# main.net
KiCad netlist of a schematic drawn in Altium Designer
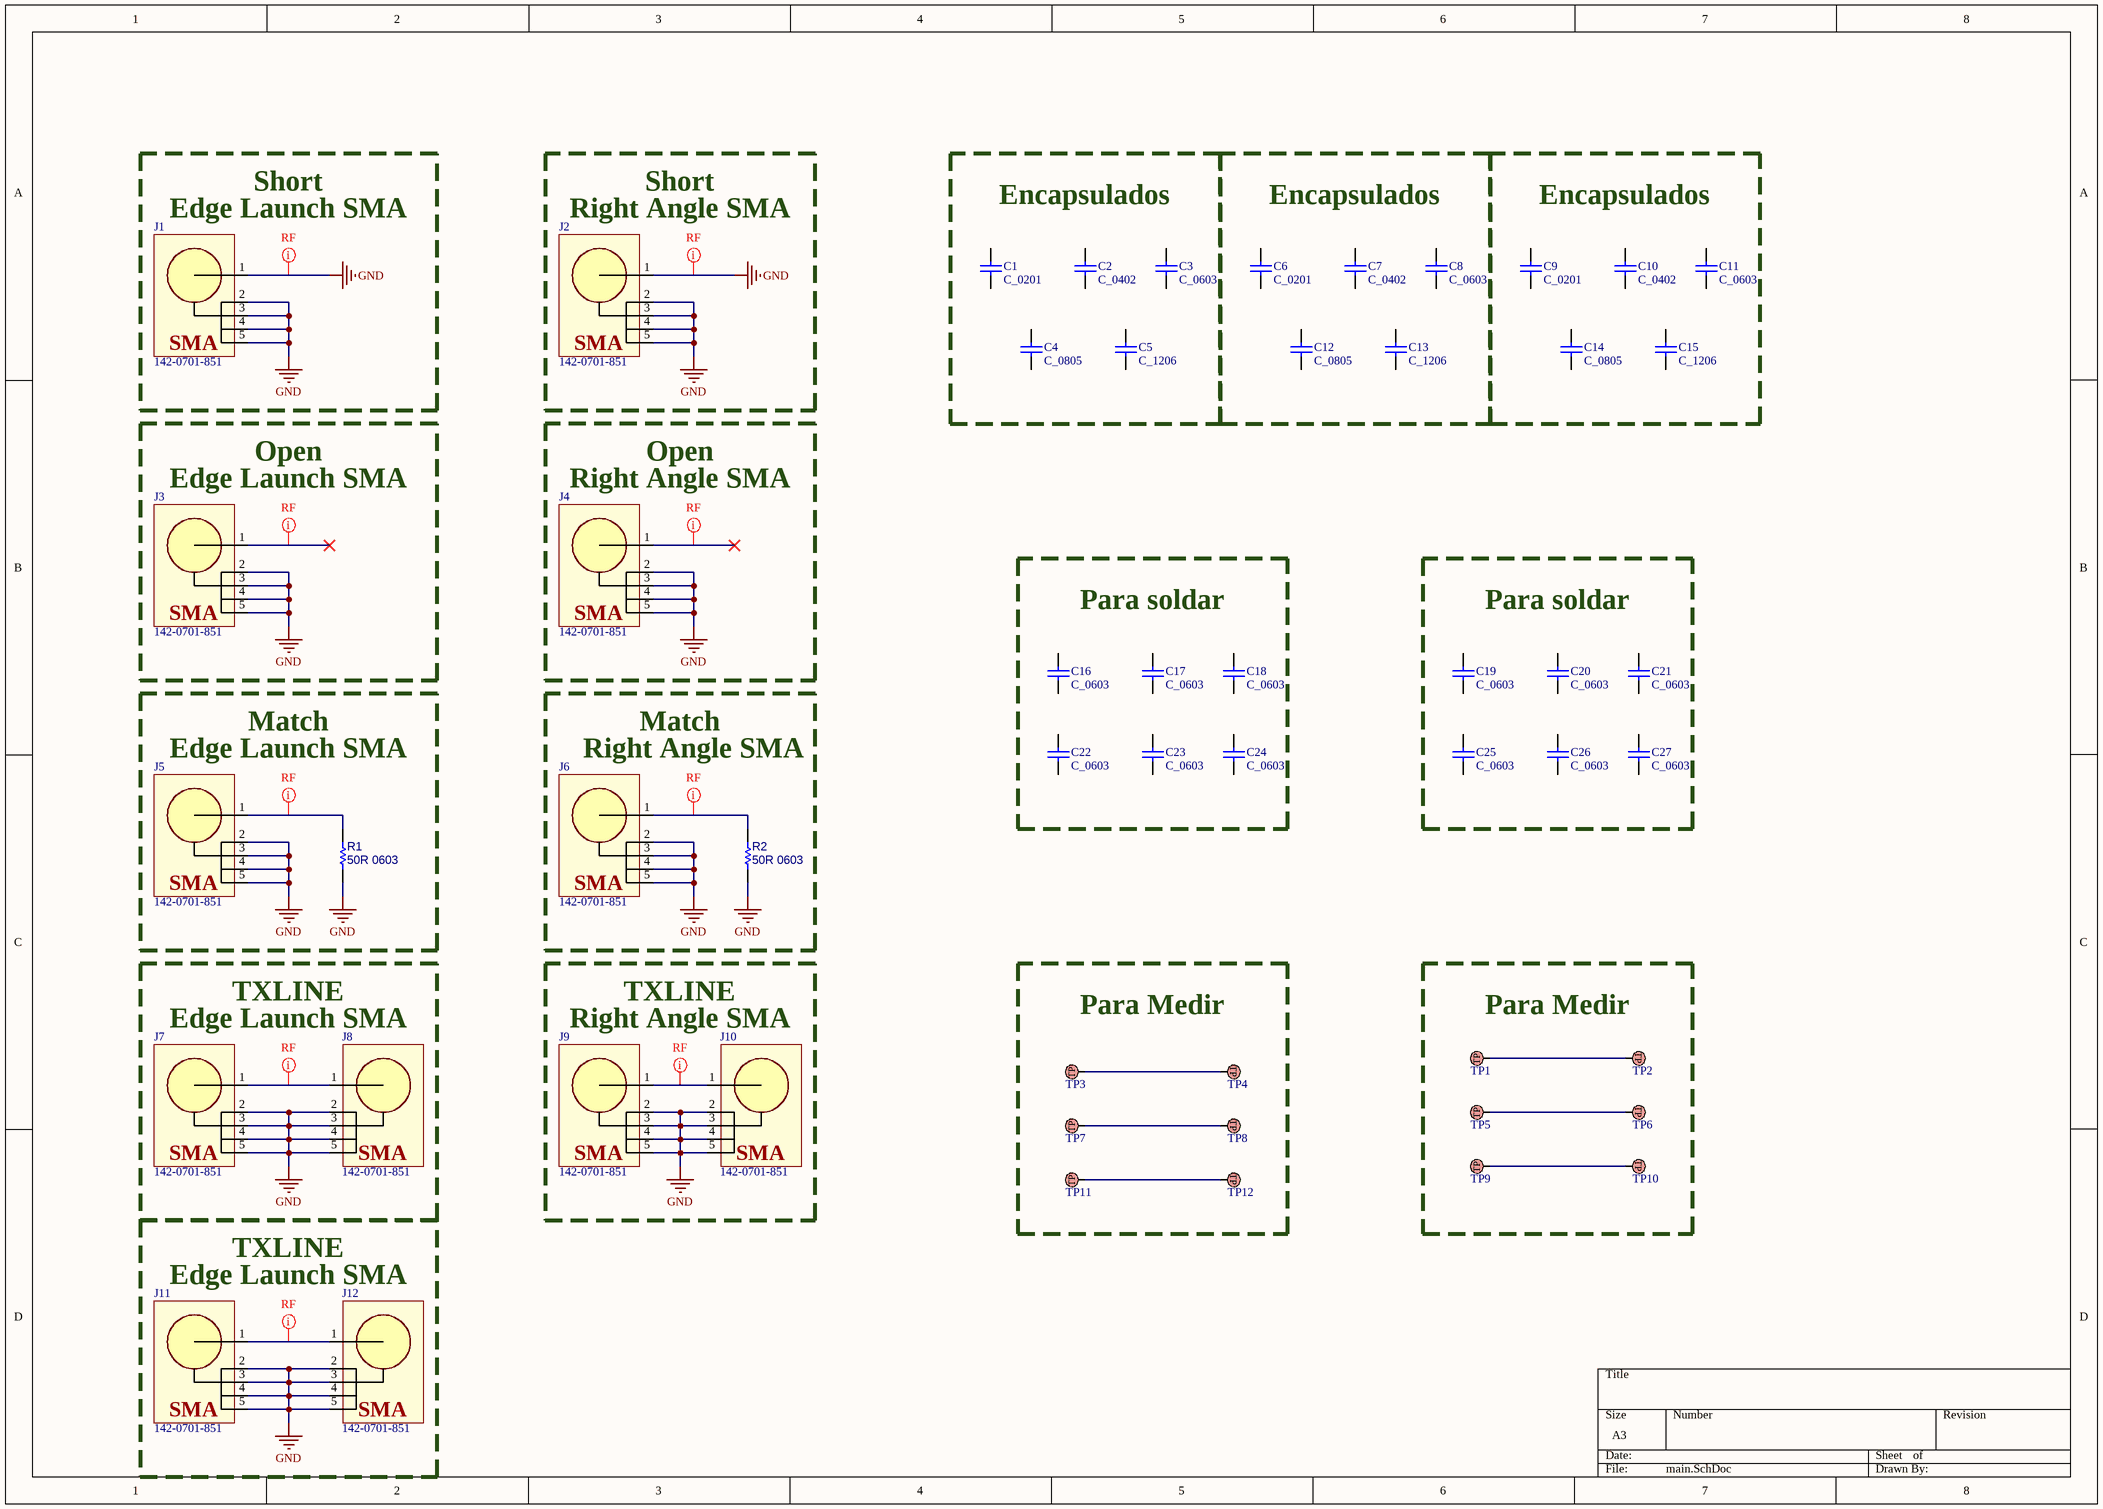
[diagram p0: main.SchDoc]

(export (version "E")
  (design (tool "Eeschema 10.0.6"))
  (components
    (comp (ref "C1")
      (value "C_0201")
      (footprint "C_0201")
      (description "Capacitor")
      (libsource (lib "SymbolsStd") (part "Cap"))
    )
    (comp (ref "C2")
      (value "C_0402")
      (footprint "C_0402")
      (description "Capacitor")
      (libsource (lib "SymbolsStd") (part "Cap"))
    )
    (comp (ref "C3")
      (value "C_0603")
      (footprint "C_0603")
      (description "Capacitor")
      (libsource (lib "SymbolsStd") (part "Cap"))
    )
    (comp (ref "C4")
      (value "C_0805")
      (footprint "C_0805")
      (description "Capacitor")
      (libsource (lib "SymbolsStd") (part "Cap"))
    )
    (comp (ref "C5")
      (value "C_1206")
      (footprint "C_1206")
      (description "Capacitor")
      (libsource (lib "SymbolsStd") (part "Cap"))
    )
    (comp (ref "C6")
      (value "C_0201")
      (footprint "C_0201")
      (description "Capacitor")
      (libsource (lib "SymbolsStd") (part "Cap"))
    )
    (comp (ref "C7")
      (value "C_0402")
      (footprint "C_0402")
      (description "Capacitor")
      (libsource (lib "SymbolsStd") (part "Cap"))
    )
    (comp (ref "C8")
      (value "C_0603")
      (footprint "C_0603")
      (description "Capacitor")
      (libsource (lib "SymbolsStd") (part "Cap"))
    )
    (comp (ref "C9")
      (value "C_0201")
      (footprint "C_0201")
      (description "Capacitor")
      (libsource (lib "SymbolsStd") (part "Cap"))
    )
    (comp (ref "C10")
      (value "C_0402")
      (footprint "C_0402")
      (description "Capacitor")
      (libsource (lib "SymbolsStd") (part "Cap"))
    )
    (comp (ref "C11")
      (value "C_0603")
      (footprint "C_0603")
      (description "Capacitor")
      (libsource (lib "SymbolsStd") (part "Cap"))
    )
    (comp (ref "C12")
      (value "C_0805")
      (footprint "C_0805")
      (description "Capacitor")
      (libsource (lib "SymbolsStd") (part "Cap"))
    )
    (comp (ref "C13")
      (value "C_1206")
      (footprint "C_1206")
      (description "Capacitor")
      (libsource (lib "SymbolsStd") (part "Cap"))
    )
    (comp (ref "C14")
      (value "C_0805")
      (footprint "C_0805")
      (description "Capacitor")
      (libsource (lib "SymbolsStd") (part "Cap"))
    )
    (comp (ref "C15")
      (value "C_1206")
      (footprint "C_1206")
      (description "Capacitor")
      (libsource (lib "SymbolsStd") (part "Cap"))
    )
    (comp (ref "C16")
      (value "C_0603")
      (footprint "C_0603")
      (description "Capacitor")
      (libsource (lib "SymbolsStd") (part "Cap"))
    )
    (comp (ref "C17")
      (value "C_0603")
      (footprint "C_0603")
      (description "Capacitor")
      (libsource (lib "SymbolsStd") (part "Cap"))
    )
    (comp (ref "C18")
      (value "C_0603")
      (footprint "C_0603")
      (description "Capacitor")
      (libsource (lib "SymbolsStd") (part "Cap"))
    )
    (comp (ref "C19")
      (value "C_0603")
      (footprint "C_0603")
      (description "Capacitor")
      (libsource (lib "SymbolsStd") (part "Cap"))
    )
    (comp (ref "C20")
      (value "C_0603")
      (footprint "C_0603")
      (description "Capacitor")
      (libsource (lib "SymbolsStd") (part "Cap"))
    )
    (comp (ref "C21")
      (value "C_0603")
      (footprint "C_0603")
      (description "Capacitor")
      (libsource (lib "SymbolsStd") (part "Cap"))
    )
    (comp (ref "C22")
      (value "C_0603")
      (footprint "C_0603")
      (description "Capacitor")
      (libsource (lib "SymbolsStd") (part "Cap"))
    )
    (comp (ref "C23")
      (value "C_0603")
      (footprint "C_0603")
      (description "Capacitor")
      (libsource (lib "SymbolsStd") (part "Cap"))
    )
    (comp (ref "C24")
      (value "C_0603")
      (footprint "C_0603")
      (description "Capacitor")
      (libsource (lib "SymbolsStd") (part "Cap"))
    )
    (comp (ref "C25")
      (value "C_0603")
      (footprint "C_0603")
      (description "Capacitor")
      (libsource (lib "SymbolsStd") (part "Cap"))
    )
    (comp (ref "C26")
      (value "C_0603")
      (footprint "C_0603")
      (description "Capacitor")
      (libsource (lib "SymbolsStd") (part "Cap"))
    )
    (comp (ref "C27")
      (value "C_0603")
      (footprint "C_0603")
      (description "Capacitor")
      (libsource (lib "SymbolsStd") (part "Cap"))
    )
    (comp (ref "J1")
      (value "142-0701-851")
      (footprint "142-0701-851")
      (description "SMA - Edge Launch - Jack (Socket)")
      (libsource (lib "SymbolsHW003") (part "142-0701-851"))
    )
    (comp (ref "J2")
      (value "142-0701-851")
      (footprint "142-0701-851")
      (description "SMA - Edge Launch - Jack (Socket)")
      (libsource (lib "SymbolsHW003") (part "142-0701-851"))
    )
    (comp (ref "J3")
      (value "142-0701-851")
      (footprint "142-0701-851")
      (description "SMA - Edge Launch - Jack (Socket)")
      (libsource (lib "SymbolsHW003") (part "142-0701-851"))
    )
    (comp (ref "J4")
      (value "142-0701-851")
      (footprint "142-0701-851")
      (description "SMA - Edge Launch - Jack (Socket)")
      (libsource (lib "SymbolsHW003") (part "142-0701-851"))
    )
    (comp (ref "J5")
      (value "142-0701-851")
      (footprint "142-0701-851")
      (description "SMA - Edge Launch - Jack (Socket)")
      (libsource (lib "SymbolsHW003") (part "142-0701-851"))
    )
    (comp (ref "J6")
      (value "142-0701-851")
      (footprint "142-0701-851")
      (description "SMA - Edge Launch - Jack (Socket)")
      (libsource (lib "SymbolsHW003") (part "142-0701-851"))
    )
    (comp (ref "J7")
      (value "142-0701-851")
      (footprint "142-0701-851")
      (description "SMA - Edge Launch - Jack (Socket)")
      (libsource (lib "SymbolsHW003") (part "142-0701-851"))
    )
    (comp (ref "J8")
      (value "142-0701-851")
      (footprint "142-0701-851")
      (description "SMA - Edge Launch - Jack (Socket)")
      (libsource (lib "") (part "142-0701-851_1"))
    )
    (comp (ref "J9")
      (value "142-0701-851")
      (footprint "142-0701-851")
      (description "SMA - Edge Launch - Jack (Socket)")
      (libsource (lib "SymbolsHW003") (part "142-0701-851"))
    )
    (comp (ref "J10")
      (value "142-0701-851")
      (footprint "142-0701-851")
      (description "SMA - Edge Launch - Jack (Socket)")
      (libsource (lib "") (part "142-0701-851_1"))
    )
    (comp (ref "J11")
      (value "142-0701-851")
      (footprint "142-0701-851")
      (description "SMA - Edge Launch - Jack (Socket)")
      (libsource (lib "SymbolsHW003") (part "142-0701-851"))
    )
    (comp (ref "J12")
      (value "142-0701-851")
      (footprint "142-0701-851")
      (description "SMA - Edge Launch - Jack (Socket)")
      (libsource (lib "") (part "142-0701-851_1"))
    )
    (comp (ref "R1")
      (value "50R 0603")
      (footprint "0603[1608]")
      (description "Resistor")
      (libsource (lib "SymbolsStd") (part "Res"))
    )
    (comp (ref "R2")
      (value "50R 0603")
      (footprint "0603[1608]")
      (description "Resistor")
      (libsource (lib "SymbolsStd") (part "Res"))
    )
    (comp (ref "TP1")
      (value "Single Pin Test Point")
      (footprint "testpoint_SMD")
      (libsource (lib "SymbolsStd") (part "Testpoint"))
    )
    (comp (ref "TP2")
      (value "Single Pin Test Point")
      (footprint "testpoint_SMD")
      (libsource (lib "SymbolsStd") (part "Testpoint"))
    )
    (comp (ref "TP3")
      (value "Single Pin Test Point")
      (footprint "testpoint_SMD")
      (libsource (lib "SymbolsStd") (part "Testpoint"))
    )
    (comp (ref "TP4")
      (value "Single Pin Test Point")
      (footprint "testpoint_SMD")
      (libsource (lib "SymbolsStd") (part "Testpoint"))
    )
    (comp (ref "TP5")
      (value "Single Pin Test Point")
      (footprint "testpoint_SMD")
      (libsource (lib "SymbolsStd") (part "Testpoint"))
    )
    (comp (ref "TP6")
      (value "Single Pin Test Point")
      (footprint "testpoint_SMD")
      (libsource (lib "SymbolsStd") (part "Testpoint"))
    )
    (comp (ref "TP7")
      (value "Single Pin Test Point")
      (footprint "testpoint_SMD")
      (libsource (lib "SymbolsStd") (part "Testpoint"))
    )
    (comp (ref "TP8")
      (value "Single Pin Test Point")
      (footprint "testpoint_SMD")
      (libsource (lib "SymbolsStd") (part "Testpoint"))
    )
    (comp (ref "TP9")
      (value "Single Pin Test Point")
      (footprint "testpoint_SMD")
      (libsource (lib "SymbolsStd") (part "Testpoint"))
    )
    (comp (ref "TP10")
      (value "Single Pin Test Point")
      (footprint "testpoint_SMD")
      (libsource (lib "SymbolsStd") (part "Testpoint"))
    )
    (comp (ref "TP11")
      (value "Single Pin Test Point")
      (footprint "testpoint_SMD")
      (libsource (lib "SymbolsStd") (part "Testpoint"))
    )
    (comp (ref "TP12")
      (value "Single Pin Test Point")
      (footprint "testpoint_SMD")
      (libsource (lib "SymbolsStd") (part "Testpoint"))
    )
  )
  (nets
    (net (code "1") (name "GND") (class "Default")
      (node (ref "J1") (pin "1") (pinfunction "1_1") (pintype "passive"))
      (node (ref "J1") (pin "2") (pinfunction "2_2") (pintype "passive"))
      (node (ref "J1") (pin "3") (pinfunction "3_3") (pintype "passive"))
      (node (ref "J1") (pin "4") (pinfunction "4_4") (pintype "passive"))
      (node (ref "J1") (pin "5") (pinfunction "5_5") (pintype "passive"))
      (node (ref "J10") (pin "2") (pinfunction "2_2") (pintype "passive"))
      (node (ref "J10") (pin "3") (pinfunction "3_3") (pintype "passive"))
      (node (ref "J10") (pin "4") (pinfunction "4_4") (pintype "passive"))
      (node (ref "J10") (pin "5") (pinfunction "5_5") (pintype "passive"))
      (node (ref "J11") (pin "2") (pinfunction "2_2") (pintype "passive"))
      (node (ref "J11") (pin "3") (pinfunction "3_3") (pintype "passive"))
      (node (ref "J11") (pin "4") (pinfunction "4_4") (pintype "passive"))
      (node (ref "J11") (pin "5") (pinfunction "5_5") (pintype "passive"))
      (node (ref "J12") (pin "2") (pinfunction "2_2") (pintype "passive"))
      (node (ref "J12") (pin "3") (pinfunction "3_3") (pintype "passive"))
      (node (ref "J12") (pin "4") (pinfunction "4_4") (pintype "passive"))
      (node (ref "J12") (pin "5") (pinfunction "5_5") (pintype "passive"))
      (node (ref "J2") (pin "1") (pinfunction "1_1") (pintype "passive"))
      (node (ref "J2") (pin "2") (pinfunction "2_2") (pintype "passive"))
      (node (ref "J2") (pin "3") (pinfunction "3_3") (pintype "passive"))
      (node (ref "J2") (pin "4") (pinfunction "4_4") (pintype "passive"))
      (node (ref "J2") (pin "5") (pinfunction "5_5") (pintype "passive"))
      (node (ref "J3") (pin "2") (pinfunction "2_2") (pintype "passive"))
      (node (ref "J3") (pin "3") (pinfunction "3_3") (pintype "passive"))
      (node (ref "J3") (pin "4") (pinfunction "4_4") (pintype "passive"))
      (node (ref "J3") (pin "5") (pinfunction "5_5") (pintype "passive"))
      (node (ref "J4") (pin "2") (pinfunction "2_2") (pintype "passive"))
      (node (ref "J4") (pin "3") (pinfunction "3_3") (pintype "passive"))
      (node (ref "J4") (pin "4") (pinfunction "4_4") (pintype "passive"))
      (node (ref "J4") (pin "5") (pinfunction "5_5") (pintype "passive"))
      (node (ref "J5") (pin "2") (pinfunction "2_2") (pintype "passive"))
      (node (ref "J5") (pin "3") (pinfunction "3_3") (pintype "passive"))
      (node (ref "J5") (pin "4") (pinfunction "4_4") (pintype "passive"))
      (node (ref "J5") (pin "5") (pinfunction "5_5") (pintype "passive"))
      (node (ref "J6") (pin "2") (pinfunction "2_2") (pintype "passive"))
      (node (ref "J6") (pin "3") (pinfunction "3_3") (pintype "passive"))
      (node (ref "J6") (pin "4") (pinfunction "4_4") (pintype "passive"))
      (node (ref "J6") (pin "5") (pinfunction "5_5") (pintype "passive"))
      (node (ref "J7") (pin "2") (pinfunction "2_2") (pintype "passive"))
      (node (ref "J7") (pin "3") (pinfunction "3_3") (pintype "passive"))
      (node (ref "J7") (pin "4") (pinfunction "4_4") (pintype "passive"))
      (node (ref "J7") (pin "5") (pinfunction "5_5") (pintype "passive"))
      (node (ref "J8") (pin "2") (pinfunction "2_2") (pintype "passive"))
      (node (ref "J8") (pin "3") (pinfunction "3_3") (pintype "passive"))
      (node (ref "J8") (pin "4") (pinfunction "4_4") (pintype "passive"))
      (node (ref "J8") (pin "5") (pinfunction "5_5") (pintype "passive"))
      (node (ref "J9") (pin "2") (pinfunction "2_2") (pintype "passive"))
      (node (ref "J9") (pin "3") (pinfunction "3_3") (pintype "passive"))
      (node (ref "J9") (pin "4") (pinfunction "4_4") (pintype "passive"))
      (node (ref "J9") (pin "5") (pinfunction "5_5") (pintype "passive"))
      (node (ref "R1") (pin "1") (pinfunction "1_1") (pintype "passive"))
      (node (ref "R2") (pin "1") (pinfunction "1_1") (pintype "passive"))
    )
    (net (code "2") (name "Net-(J5-Pad1)") (class "Default")
      (node (ref "J5") (pin "1") (pinfunction "1_1") (pintype "passive"))
      (node (ref "R1") (pin "2") (pinfunction "2_2") (pintype "passive"))
    )
    (net (code "3") (name "Net-(J6-Pad1)") (class "Default")
      (node (ref "J6") (pin "1") (pinfunction "1_1") (pintype "passive"))
      (node (ref "R2") (pin "2") (pinfunction "2_2") (pintype "passive"))
    )
    (net (code "4") (name "Net-(J7-Pad1)") (class "Default")
      (node (ref "J7") (pin "1") (pinfunction "1_1") (pintype "passive"))
      (node (ref "J8") (pin "1") (pinfunction "1_1") (pintype "passive"))
    )
    (net (code "5") (name "Net-(J10-Pad1)") (class "Default")
      (node (ref "J10") (pin "1") (pinfunction "1_1") (pintype "passive"))
      (node (ref "J9") (pin "1") (pinfunction "1_1") (pintype "passive"))
    )
    (net (code "6") (name "Net-(J11-Pad1)") (class "Default")
      (node (ref "J11") (pin "1") (pinfunction "1_1") (pintype "passive"))
      (node (ref "J12") (pin "1") (pinfunction "1_1") (pintype "passive"))
    )
    (net (code "7") (name "Net-(TP1-Pad0)") (class "Default")
      (node (ref "TP1") (pin "0") (pinfunction "0_0") (pintype "passive"))
      (node (ref "TP2") (pin "0") (pinfunction "0_0") (pintype "passive"))
    )
    (net (code "8") (name "Net-(TP3-Pad0)") (class "Default")
      (node (ref "TP3") (pin "0") (pinfunction "0_0") (pintype "passive"))
      (node (ref "TP4") (pin "0") (pinfunction "0_0") (pintype "passive"))
    )
    (net (code "9") (name "Net-(TP5-Pad0)") (class "Default")
      (node (ref "TP5") (pin "0") (pinfunction "0_0") (pintype "passive"))
      (node (ref "TP6") (pin "0") (pinfunction "0_0") (pintype "passive"))
    )
    (net (code "10") (name "Net-(TP7-Pad0)") (class "Default")
      (node (ref "TP7") (pin "0") (pinfunction "0_0") (pintype "passive"))
      (node (ref "TP8") (pin "0") (pinfunction "0_0") (pintype "passive"))
    )
    (net (code "11") (name "Net-(TP10-Pad0)") (class "Default")
      (node (ref "TP10") (pin "0") (pinfunction "0_0") (pintype "passive"))
      (node (ref "TP9") (pin "0") (pinfunction "0_0") (pintype "passive"))
    )
    (net (code "12") (name "Net-(TP11-Pad0)") (class "Default")
      (node (ref "TP11") (pin "0") (pinfunction "0_0") (pintype "passive"))
      (node (ref "TP12") (pin "0") (pinfunction "0_0") (pintype "passive"))
    )
    (net (code "13") (name "unconnected-(C1-Pad1)") (class "Default")
      (node (ref "C1") (pin "1") (pinfunction "1_1") (pintype "passive"))
    )
    (net (code "14") (name "unconnected-(C1-Pad2)") (class "Default")
      (node (ref "C1") (pin "2") (pinfunction "2_2") (pintype "passive"))
    )
    (net (code "15") (name "unconnected-(C2-Pad1)") (class "Default")
      (node (ref "C2") (pin "1") (pinfunction "1_1") (pintype "passive"))
    )
    (net (code "16") (name "unconnected-(C2-Pad2)") (class "Default")
      (node (ref "C2") (pin "2") (pinfunction "2_2") (pintype "passive"))
    )
    (net (code "17") (name "unconnected-(C3-Pad1)") (class "Default")
      (node (ref "C3") (pin "1") (pinfunction "1_1") (pintype "passive"))
    )
    (net (code "18") (name "unconnected-(C3-Pad2)") (class "Default")
      (node (ref "C3") (pin "2") (pinfunction "2_2") (pintype "passive"))
    )
    (net (code "19") (name "unconnected-(C4-Pad1)") (class "Default")
      (node (ref "C4") (pin "1") (pinfunction "1_1") (pintype "passive"))
    )
    (net (code "20") (name "unconnected-(C4-Pad2)") (class "Default")
      (node (ref "C4") (pin "2") (pinfunction "2_2") (pintype "passive"))
    )
    (net (code "21") (name "unconnected-(C5-Pad1)") (class "Default")
      (node (ref "C5") (pin "1") (pinfunction "1_1") (pintype "passive"))
    )
    (net (code "22") (name "unconnected-(C5-Pad2)") (class "Default")
      (node (ref "C5") (pin "2") (pinfunction "2_2") (pintype "passive"))
    )
    (net (code "23") (name "unconnected-(C6-Pad1)") (class "Default")
      (node (ref "C6") (pin "1") (pinfunction "1_1") (pintype "passive"))
    )
    (net (code "24") (name "unconnected-(C6-Pad2)") (class "Default")
      (node (ref "C6") (pin "2") (pinfunction "2_2") (pintype "passive"))
    )
    (net (code "25") (name "unconnected-(C7-Pad1)") (class "Default")
      (node (ref "C7") (pin "1") (pinfunction "1_1") (pintype "passive"))
    )
    (net (code "26") (name "unconnected-(C7-Pad2)") (class "Default")
      (node (ref "C7") (pin "2") (pinfunction "2_2") (pintype "passive"))
    )
    (net (code "27") (name "unconnected-(C8-Pad1)") (class "Default")
      (node (ref "C8") (pin "1") (pinfunction "1_1") (pintype "passive"))
    )
    (net (code "28") (name "unconnected-(C8-Pad2)") (class "Default")
      (node (ref "C8") (pin "2") (pinfunction "2_2") (pintype "passive"))
    )
    (net (code "29") (name "unconnected-(C9-Pad1)") (class "Default")
      (node (ref "C9") (pin "1") (pinfunction "1_1") (pintype "passive"))
    )
    (net (code "30") (name "unconnected-(C9-Pad2)") (class "Default")
      (node (ref "C9") (pin "2") (pinfunction "2_2") (pintype "passive"))
    )
    (net (code "31") (name "unconnected-(C10-Pad1)") (class "Default")
      (node (ref "C10") (pin "1") (pinfunction "1_1") (pintype "passive"))
    )
    (net (code "32") (name "unconnected-(C10-Pad2)") (class "Default")
      (node (ref "C10") (pin "2") (pinfunction "2_2") (pintype "passive"))
    )
    (net (code "33") (name "unconnected-(C11-Pad1)") (class "Default")
      (node (ref "C11") (pin "1") (pinfunction "1_1") (pintype "passive"))
    )
    (net (code "34") (name "unconnected-(C11-Pad2)") (class "Default")
      (node (ref "C11") (pin "2") (pinfunction "2_2") (pintype "passive"))
    )
    (net (code "35") (name "unconnected-(C12-Pad1)") (class "Default")
      (node (ref "C12") (pin "1") (pinfunction "1_1") (pintype "passive"))
    )
    (net (code "36") (name "unconnected-(C12-Pad2)") (class "Default")
      (node (ref "C12") (pin "2") (pinfunction "2_2") (pintype "passive"))
    )
    (net (code "37") (name "unconnected-(C13-Pad1)") (class "Default")
      (node (ref "C13") (pin "1") (pinfunction "1_1") (pintype "passive"))
    )
    (net (code "38") (name "unconnected-(C13-Pad2)") (class "Default")
      (node (ref "C13") (pin "2") (pinfunction "2_2") (pintype "passive"))
    )
    (net (code "39") (name "unconnected-(C14-Pad1)") (class "Default")
      (node (ref "C14") (pin "1") (pinfunction "1_1") (pintype "passive"))
    )
    (net (code "40") (name "unconnected-(C14-Pad2)") (class "Default")
      (node (ref "C14") (pin "2") (pinfunction "2_2") (pintype "passive"))
    )
    (net (code "41") (name "unconnected-(C15-Pad1)") (class "Default")
      (node (ref "C15") (pin "1") (pinfunction "1_1") (pintype "passive"))
    )
    (net (code "42") (name "unconnected-(C15-Pad2)") (class "Default")
      (node (ref "C15") (pin "2") (pinfunction "2_2") (pintype "passive"))
    )
    (net (code "43") (name "unconnected-(C16-Pad1)") (class "Default")
      (node (ref "C16") (pin "1") (pinfunction "1_1") (pintype "passive"))
    )
    (net (code "44") (name "unconnected-(C16-Pad2)") (class "Default")
      (node (ref "C16") (pin "2") (pinfunction "2_2") (pintype "passive"))
    )
    (net (code "45") (name "unconnected-(C17-Pad1)") (class "Default")
      (node (ref "C17") (pin "1") (pinfunction "1_1") (pintype "passive"))
    )
    (net (code "46") (name "unconnected-(C17-Pad2)") (class "Default")
      (node (ref "C17") (pin "2") (pinfunction "2_2") (pintype "passive"))
    )
    (net (code "47") (name "unconnected-(C18-Pad1)") (class "Default")
      (node (ref "C18") (pin "1") (pinfunction "1_1") (pintype "passive"))
    )
    (net (code "48") (name "unconnected-(C18-Pad2)") (class "Default")
      (node (ref "C18") (pin "2") (pinfunction "2_2") (pintype "passive"))
    )
    (net (code "49") (name "unconnected-(C19-Pad1)") (class "Default")
      (node (ref "C19") (pin "1") (pinfunction "1_1") (pintype "passive"))
    )
    (net (code "50") (name "unconnected-(C19-Pad2)") (class "Default")
      (node (ref "C19") (pin "2") (pinfunction "2_2") (pintype "passive"))
    )
    (net (code "51") (name "unconnected-(C20-Pad1)") (class "Default")
      (node (ref "C20") (pin "1") (pinfunction "1_1") (pintype "passive"))
    )
    (net (code "52") (name "unconnected-(C20-Pad2)") (class "Default")
      (node (ref "C20") (pin "2") (pinfunction "2_2") (pintype "passive"))
    )
    (net (code "53") (name "unconnected-(C21-Pad1)") (class "Default")
      (node (ref "C21") (pin "1") (pinfunction "1_1") (pintype "passive"))
    )
    (net (code "54") (name "unconnected-(C21-Pad2)") (class "Default")
      (node (ref "C21") (pin "2") (pinfunction "2_2") (pintype "passive"))
    )
    (net (code "55") (name "unconnected-(C22-Pad1)") (class "Default")
      (node (ref "C22") (pin "1") (pinfunction "1_1") (pintype "passive"))
    )
    (net (code "56") (name "unconnected-(C22-Pad2)") (class "Default")
      (node (ref "C22") (pin "2") (pinfunction "2_2") (pintype "passive"))
    )
    (net (code "57") (name "unconnected-(C23-Pad1)") (class "Default")
      (node (ref "C23") (pin "1") (pinfunction "1_1") (pintype "passive"))
    )
    (net (code "58") (name "unconnected-(C23-Pad2)") (class "Default")
      (node (ref "C23") (pin "2") (pinfunction "2_2") (pintype "passive"))
    )
    (net (code "59") (name "unconnected-(C24-Pad1)") (class "Default")
      (node (ref "C24") (pin "1") (pinfunction "1_1") (pintype "passive"))
    )
    (net (code "60") (name "unconnected-(C24-Pad2)") (class "Default")
      (node (ref "C24") (pin "2") (pinfunction "2_2") (pintype "passive"))
    )
    (net (code "61") (name "unconnected-(C25-Pad1)") (class "Default")
      (node (ref "C25") (pin "1") (pinfunction "1_1") (pintype "passive"))
    )
    (net (code "62") (name "unconnected-(C25-Pad2)") (class "Default")
      (node (ref "C25") (pin "2") (pinfunction "2_2") (pintype "passive"))
    )
    (net (code "63") (name "unconnected-(C26-Pad1)") (class "Default")
      (node (ref "C26") (pin "1") (pinfunction "1_1") (pintype "passive"))
    )
    (net (code "64") (name "unconnected-(C26-Pad2)") (class "Default")
      (node (ref "C26") (pin "2") (pinfunction "2_2") (pintype "passive"))
    )
    (net (code "65") (name "unconnected-(C27-Pad1)") (class "Default")
      (node (ref "C27") (pin "1") (pinfunction "1_1") (pintype "passive"))
    )
    (net (code "66") (name "unconnected-(C27-Pad2)") (class "Default")
      (node (ref "C27") (pin "2") (pinfunction "2_2") (pintype "passive"))
    )
    (net (code "67") (name "unconnected-(J3-Pad1)") (class "Default")
      (node (ref "J3") (pin "1") (pinfunction "1_1") (pintype "passive+no_connect"))
    )
    (net (code "68") (name "unconnected-(J4-Pad1)") (class "Default")
      (node (ref "J4") (pin "1") (pinfunction "1_1") (pintype "passive+no_connect"))
    )
  )
)
